# Driver_Circuit.net
KiCad netlist of a schematic drawn in Altium Designer
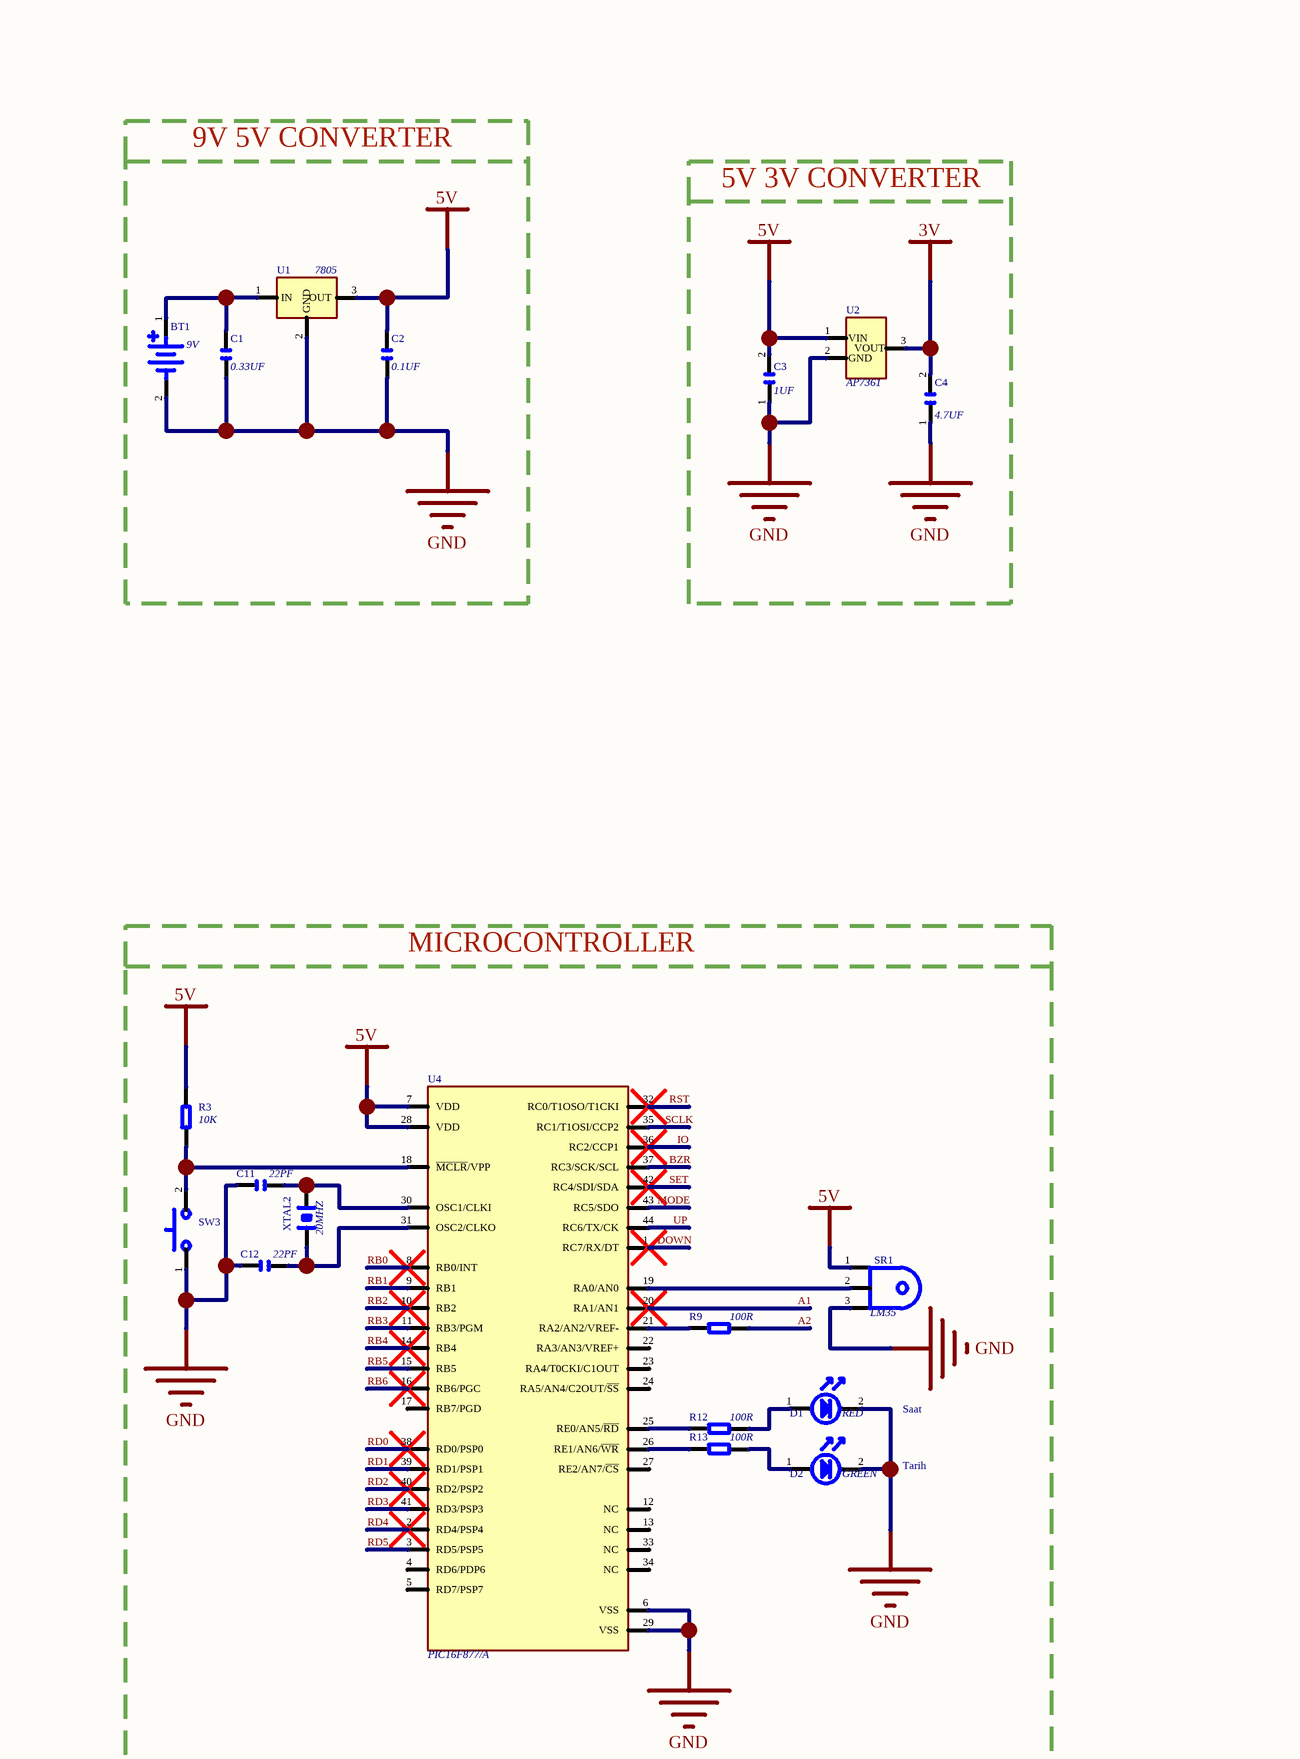
[diagram p0: Driver Circuit.SchDoc, top left]
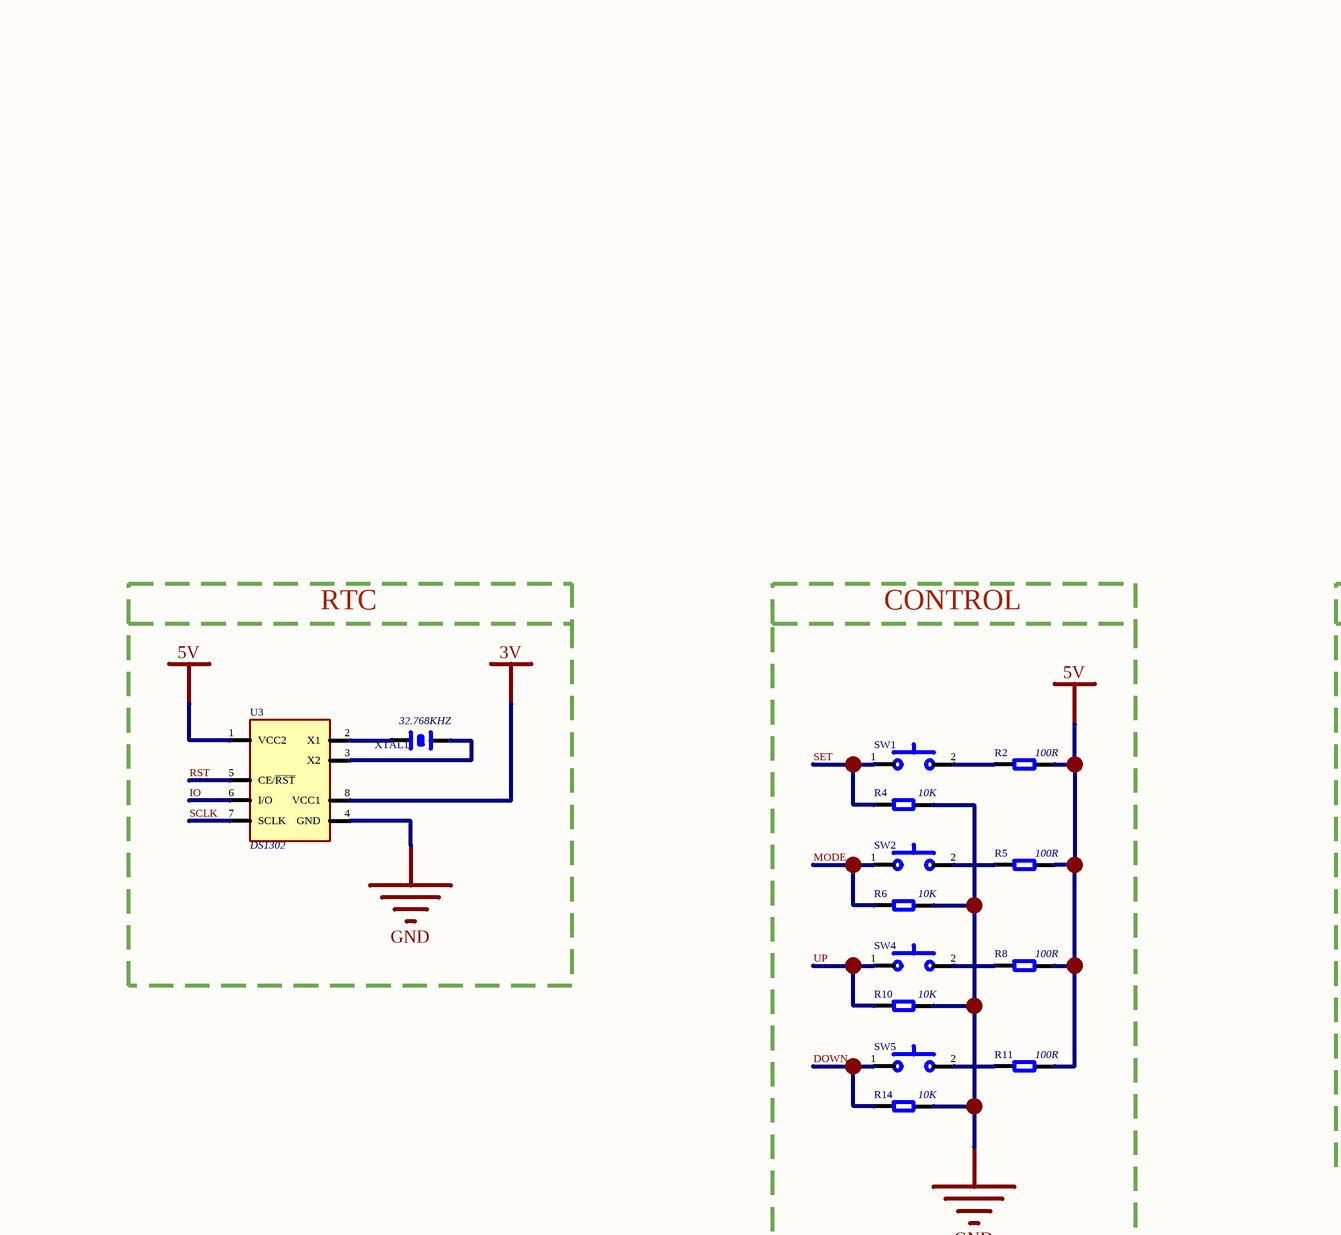
[diagram p1: Driver Circuit.SchDoc, top middle]
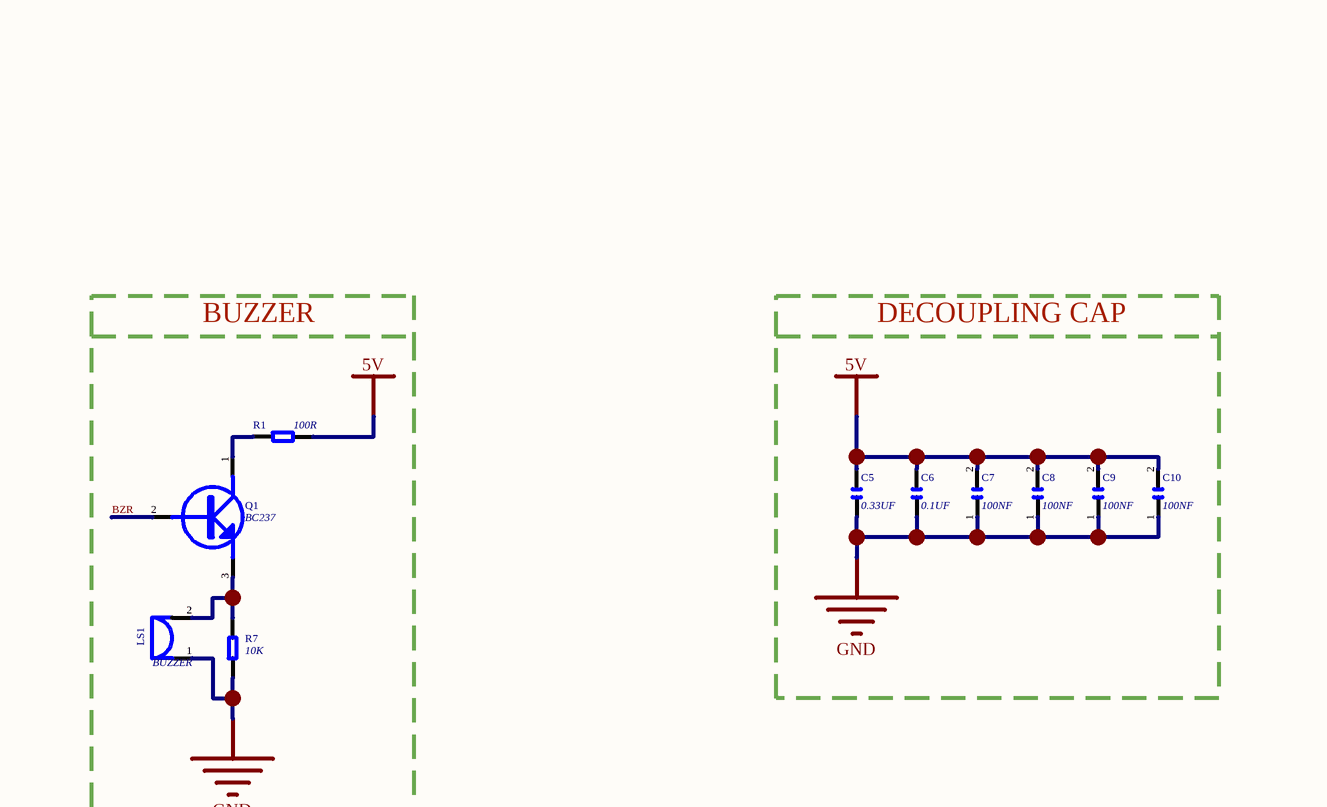
[diagram p2: Driver Circuit.SchDoc, top right]
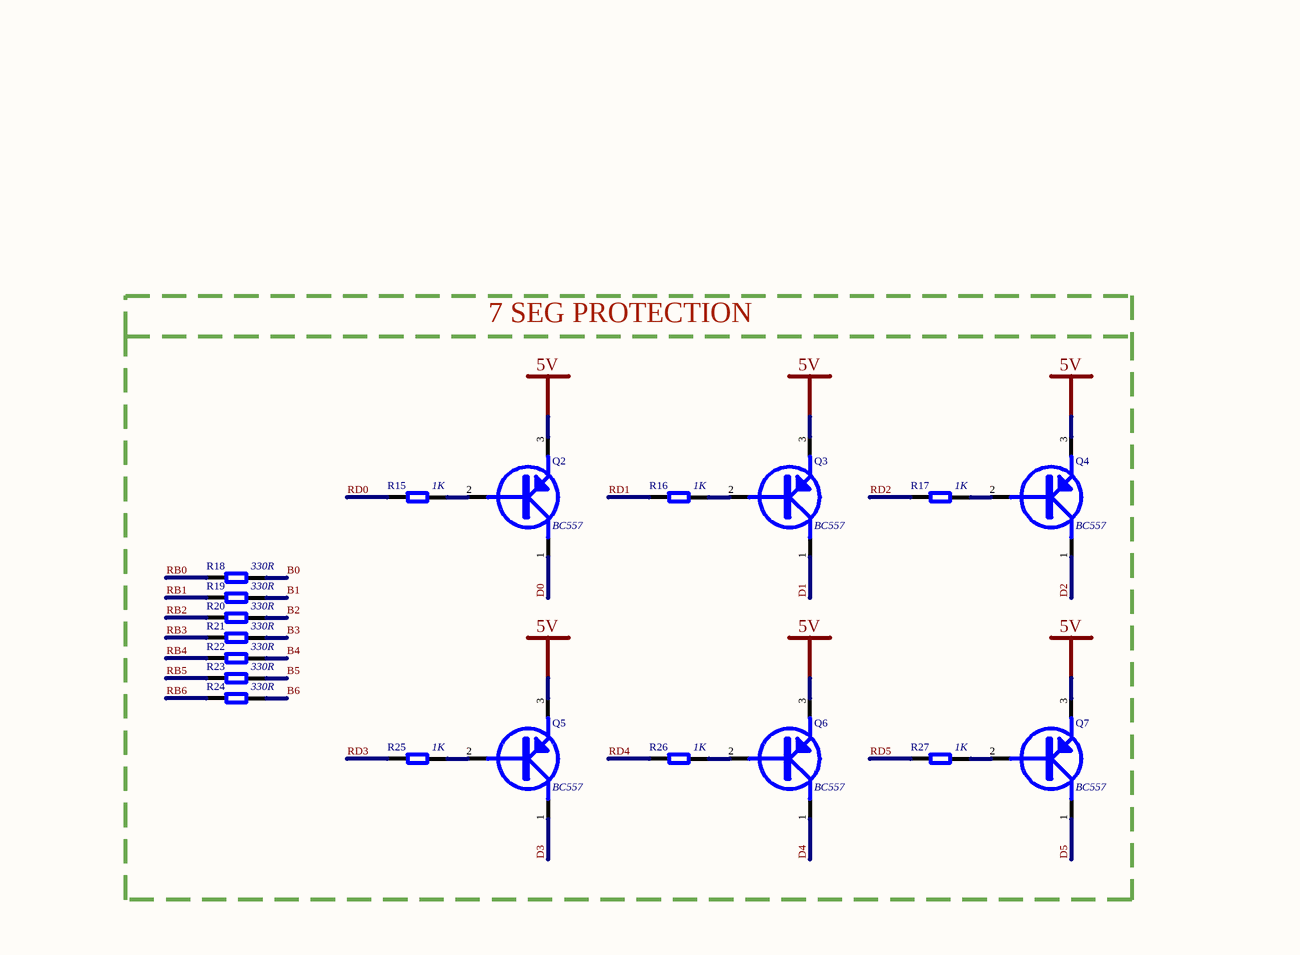
[diagram p3: Driver Circuit.SchDoc, centre left]
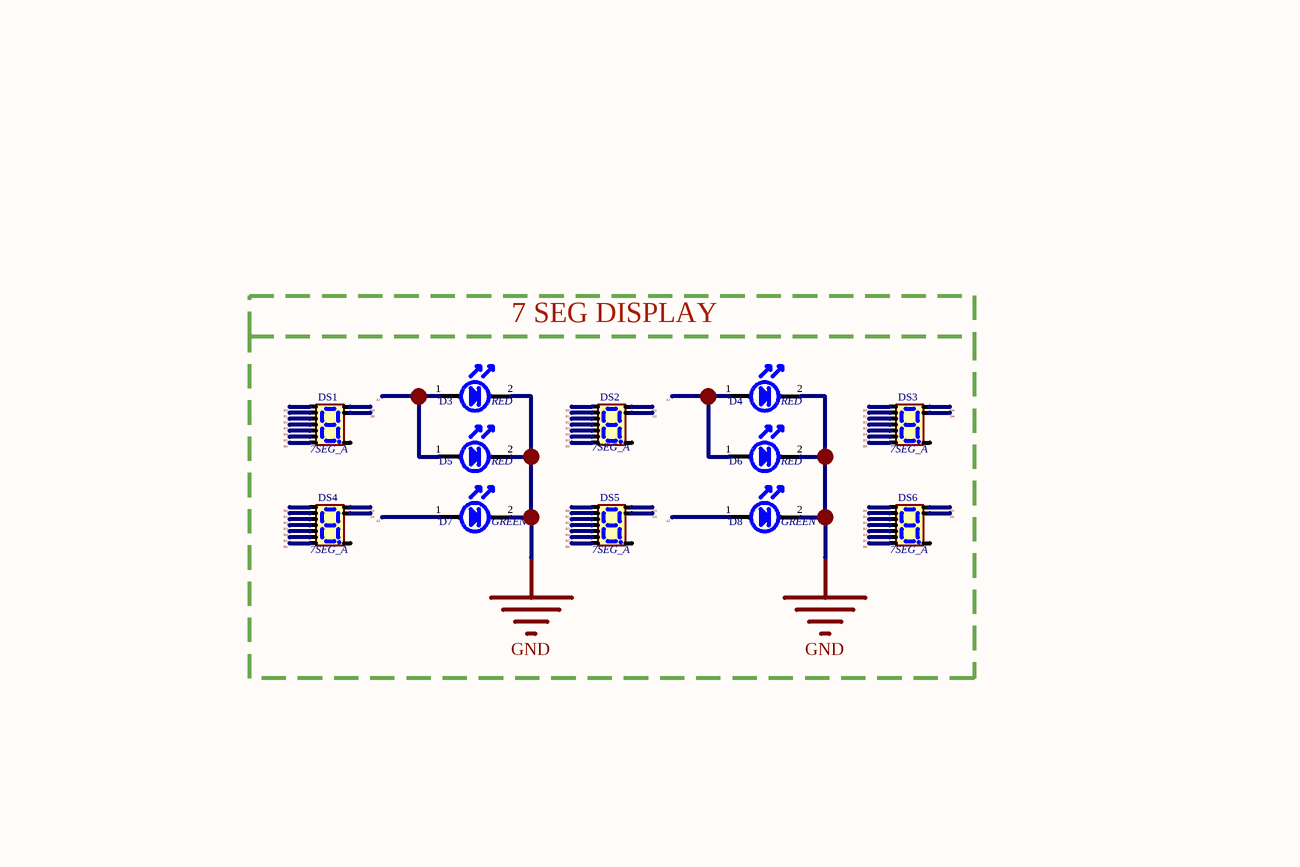
[diagram p4: Driver Circuit.SchDoc, centre middle]

(export (version "E")
  (design (tool "Eeschema 10.0.6"))
  (components
    (comp (ref "BT1")
      (value "9V")
      (footprint "BATTERY_9V")
      (fields
        (field (name "MANUFACTURER") "Memory Protection Devices")
        (field (name "MANUFACTURER PART NUMBER") "BH9VPC")
        (field (name "Comment") "BH9VPC & 6LF22XWA/B")
      )
      (libsource (lib "Integrated_Library") (part "BATTERY_9V"))
    )
    (comp (ref "C1")
      (value "GRM033R60J334ME90D")
      (footprint "CAP_0603")
      (description "CAP CER 0.33UF %20 0603 SMD")
      (fields
        (field (name "MANUFACTURER") "Murata")
        (field (name "TOLERANCE") "20%")
        (field (name "CAPACITOR") "0.33UF")
      )
      (libsource (lib "Integrated_Library") (part "0603_CAP_CER  UF_0.33"))
    )
    (comp (ref "C2")
      (value "GRM033R60J104KE19D")
      (footprint "CAP_0603")
      (description "CAP CER 0.1UF %10 0603 SMD")
      (fields
        (field (name "MANUFACTURER") "Murata")
        (field (name "TOLERANCE") "10%")
        (field (name "CAPACITOR") "0.1UF")
      )
      (libsource (lib "Integrated_Library") (part "0603_CAP_CER  UF_0.1"))
    )
    (comp (ref "C3")
      (value "CL21B105KBFNNNE")
      (footprint "CAP_0805")
      (description "CAP CER 1UF %10 0805 SMD")
      (fields (field (name "CAPACITOR") "1UF"))
      (libsource (lib "Integrated_Library") (part "0805_CAP_CER  UF_1"))
    )
    (comp (ref "C4")
      (value "CL21A475KAQNNNE")
      (footprint "CAP_0805")
      (description "CAP CER 4.7UF %10 0805 SMD")
      (fields (field (name "CAPACITOR") "4.7UF"))
      (libsource (lib "Integrated_Library") (part "0805_CAP_CER  UF_4.7"))
    )
    (comp (ref "C5")
      (value "GRM033R60J334ME90D")
      (footprint "CAP_0603")
      (description "CAP CER 0.33UF %20 0603 SMD")
      (fields
        (field (name "MANUFACTURER") "Murata")
        (field (name "TOLERANCE") "20%")
        (field (name "CAPACITOR") "0.33UF")
      )
      (libsource (lib "Integrated_Library") (part "0603_CAP_CER  UF_0.33"))
    )
    (comp (ref "C6")
      (value "GRM033R60J104KE19D")
      (footprint "CAP_0603")
      (description "CAP CER 0.1UF %10 0603 SMD")
      (fields
        (field (name "MANUFACTURER") "Murata")
        (field (name "TOLERANCE") "10%")
        (field (name "CAPACITOR") "0.1UF")
      )
      (libsource (lib "Integrated_Library") (part "0603_CAP_CER  UF_0.1"))
    )
    (comp (ref "C7")
      (value "C0603C104K5RACTU")
      (footprint "CAP_0603")
      (description "CAP CER 100NF %10 0603 SMD")
      (fields (field (name "CAPACITOR") "100NF"))
      (libsource (lib "Integrated_Library") (part "0603_CAP_CER  NF_100"))
    )
    (comp (ref "C8")
      (value "C0603C104K5RACTU")
      (footprint "CAP_0603")
      (description "CAP CER 100NF %10 0603 SMD")
      (fields (field (name "CAPACITOR") "100NF"))
      (libsource (lib "Integrated_Library") (part "0603_CAP_CER  NF_100"))
    )
    (comp (ref "C9")
      (value "C0603C104K5RACTU")
      (footprint "CAP_0603")
      (description "CAP CER 100NF %10 0603 SMD")
      (fields (field (name "CAPACITOR") "100NF"))
      (libsource (lib "Integrated_Library") (part "0603_CAP_CER  NF_100"))
    )
    (comp (ref "C10")
      (value "C0603C104K5RACTU")
      (footprint "CAP_0603")
      (description "CAP CER 100NF %10 0603 SMD")
      (fields (field (name "CAPACITOR") "100NF"))
      (libsource (lib "Integrated_Library") (part "0603_CAP_CER  NF_100"))
    )
    (comp (ref "C11")
      (value "GRM0335C1H220JA01D")
      (footprint "CAP_0603")
      (description "CAP CER 22PF %5 0603 SMD")
      (fields
        (field (name "MANUFACTURER") "Murata")
        (field (name "TOLERANCE") "5%")
        (field (name "CAPACITOR") "22PF")
      )
      (libsource (lib "Integrated_Library") (part "0603_CAP_CER  PF_22"))
    )
    (comp (ref "C12")
      (value "GRM0335C1H220JA01D")
      (footprint "CAP_0603")
      (description "CAP CER 22PF %5 0603 SMD")
      (fields
        (field (name "MANUFACTURER") "Murata")
        (field (name "TOLERANCE") "5%")
        (field (name "CAPACITOR") "22PF")
      )
      (libsource (lib "Integrated_Library") (part "0603_CAP_CER  PF_22"))
    )
    (comp (ref "D1")
      (value "LTST-C170KRKT")
      (footprint "LED RED_0805")
      (description "Red 631nm LED Indication - Discrete 2V 0805 (2012 Metric)")
      (fields (field (name "MANUFACTURER") "Vishay Lite-On") (field (name "DIODE") "RED"))
      (libsource (lib "Integrated_Library") (part "LED_0805_RED"))
    )
    (comp (ref "D2")
      (value "LTST-C171GKT")
      (footprint "LED GREEN_0805")
      (description "Green 569nm LED Indication - Discrete 2.1V 0805 (2012 Metric)")
      (fields (field (name "MANUFACTURER") "Vishay Lite-On") (field (name "DIODE") "GREEN"))
      (libsource (lib "Integrated_Library") (part "LED_0805_GREEN"))
    )
    (comp (ref "D3")
      (value "LTST-C170KRKT")
      (footprint "LED RED_0805")
      (description "Red 631nm LED Indication - Discrete 2V 0805 (2012 Metric)")
      (fields (field (name "MANUFACTURER") "Vishay Lite-On") (field (name "DIODE") "RED"))
      (libsource (lib "Integrated_Library") (part "LED_0805_RED"))
    )
    (comp (ref "D4")
      (value "LTST-C170KRKT")
      (footprint "LED RED_0805")
      (description "Red 631nm LED Indication - Discrete 2V 0805 (2012 Metric)")
      (fields (field (name "MANUFACTURER") "Vishay Lite-On") (field (name "DIODE") "RED"))
      (libsource (lib "Integrated_Library") (part "LED_0805_RED"))
    )
    (comp (ref "D5")
      (value "LTST-C170KRKT")
      (footprint "LED RED_0805")
      (description "Red 631nm LED Indication - Discrete 2V 0805 (2012 Metric)")
      (fields (field (name "MANUFACTURER") "Vishay Lite-On") (field (name "DIODE") "RED"))
      (libsource (lib "Integrated_Library") (part "LED_0805_RED"))
    )
    (comp (ref "D6")
      (value "LTST-C170KRKT")
      (footprint "LED RED_0805")
      (description "Red 631nm LED Indication - Discrete 2V 0805 (2012 Metric)")
      (fields (field (name "MANUFACTURER") "Vishay Lite-On") (field (name "DIODE") "RED"))
      (libsource (lib "Integrated_Library") (part "LED_0805_RED"))
    )
    (comp (ref "D7")
      (value "LTST-C171GKT")
      (footprint "LED GREEN_0805")
      (description "Green 569nm LED Indication - Discrete 2.1V 0805 (2012 Metric)")
      (fields (field (name "MANUFACTURER") "Vishay Lite-On") (field (name "DIODE") "GREEN"))
      (libsource (lib "Integrated_Library") (part "LED_0805_GREEN"))
    )
    (comp (ref "D8")
      (value "LTST-C171GKT")
      (footprint "LED GREEN_0805")
      (description "Green 569nm LED Indication - Discrete 2.1V 0805 (2012 Metric)")
      (fields (field (name "MANUFACTURER") "Vishay Lite-On") (field (name "DIODE") "GREEN"))
      (libsource (lib "Integrated_Library") (part "LED_0805_GREEN"))
    )
    (comp (ref "DS1")
      (value "7SEG_A")
      (footprint "7 SEG_CA_SMD_ACSX03-41")
      (fields
        (field (name "MANUFACTURER") "Kingbright")
        (field (name "MANUFACTURER PART NUMBER") "ACSA03-41SURKWA-F01")
      )
      (libsource (lib "Integrated_Library") (part "7 SEG DISP_CA_SMD"))
    )
    (comp (ref "DS2")
      (value "7SEG_A")
      (footprint "7 SEG_CA_SMD_ACSX03-41")
      (fields
        (field (name "MANUFACTURER") "Kingbright")
        (field (name "MANUFACTURER PART NUMBER") "ACSA03-41SURKWA-F01")
      )
      (libsource (lib "Integrated_Library") (part "7 SEG DISP_CA_SMD"))
    )
    (comp (ref "DS3")
      (value "7SEG_A")
      (footprint "7 SEG_CA_SMD_ACSX03-41")
      (fields
        (field (name "MANUFACTURER") "Kingbright")
        (field (name "MANUFACTURER PART NUMBER") "ACSA03-41SURKWA-F01")
      )
      (libsource (lib "Integrated_Library") (part "7 SEG DISP_CA_SMD"))
    )
    (comp (ref "DS4")
      (value "7SEG_A")
      (footprint "7 SEG_CA_SMD_ACSX03-41")
      (fields
        (field (name "MANUFACTURER") "Kingbright")
        (field (name "MANUFACTURER PART NUMBER") "ACSA03-41SURKWA-F01")
      )
      (libsource (lib "Integrated_Library") (part "7 SEG DISP_CA_SMD"))
    )
    (comp (ref "DS5")
      (value "7SEG_A")
      (footprint "7 SEG_CA_SMD_ACSX03-41")
      (fields
        (field (name "MANUFACTURER") "Kingbright")
        (field (name "MANUFACTURER PART NUMBER") "ACSA03-41SURKWA-F01")
      )
      (libsource (lib "Integrated_Library") (part "7 SEG DISP_CA_SMD"))
    )
    (comp (ref "DS6")
      (value "7SEG_A")
      (footprint "7 SEG_CA_SMD_ACSX03-41")
      (fields
        (field (name "MANUFACTURER") "Kingbright")
        (field (name "MANUFACTURER PART NUMBER") "ACSA03-41SURKWA-F01")
      )
      (libsource (lib "Integrated_Library") (part "7 SEG DISP_CA_SMD"))
    )
    (comp (ref "LS1")
      (value "BUZZER")
      (footprint "BUZZER_5V")
      (fields
        (field (name "MANUFACTURER") "Projects Unlimited")
        (field (name "MANUFACTURER PART NUMBER") "AI-1027-TWT-5V-R")
      )
      (libsource (lib "Integrated_Library") (part "BUZZER_5V"))
    )
    (comp (ref "Q1")
      (value "BC237")
      (footprint "TO-92")
      (description "Bipolar (BJT) Transistor NPN 45 V 100 mA 200MHz 350 mW Through Hole TO-92 (TO-226)")
      (fields
        (field (name "MANUFACTURER") "ON Semiconductor")
        (field (name "MANUFACTURER PART NUMBER") "BC237G")
      )
      (libsource (lib "Integrated_Library") (part "BC237"))
    )
    (comp (ref "Q2")
      (value "BC557")
      (footprint "TO-92-3")
      (description "Trans GP BJT PNP 45V 0.1A 500mW 3-Pin TO-92 Fan-Fold")
      (fields
        (field (name "MANUFACTURER") "ON Semiconductor / Fairchild")
        (field (name "MANUFACTURER PART NUMBER") "BC557BTA")
      )
      (libsource (lib "Integrated_Library") (part "BC557"))
    )
    (comp (ref "Q3")
      (value "BC557")
      (footprint "TO-92-3")
      (description "Trans GP BJT PNP 45V 0.1A 500mW 3-Pin TO-92 Fan-Fold")
      (fields
        (field (name "MANUFACTURER") "ON Semiconductor / Fairchild")
        (field (name "MANUFACTURER PART NUMBER") "BC557BTA")
      )
      (libsource (lib "Integrated_Library") (part "BC557"))
    )
    (comp (ref "Q4")
      (value "BC557")
      (footprint "TO-92-3")
      (description "Trans GP BJT PNP 45V 0.1A 500mW 3-Pin TO-92 Fan-Fold")
      (fields
        (field (name "MANUFACTURER") "ON Semiconductor / Fairchild")
        (field (name "MANUFACTURER PART NUMBER") "BC557BTA")
      )
      (libsource (lib "Integrated_Library") (part "BC557"))
    )
    (comp (ref "Q5")
      (value "BC557")
      (footprint "TO-92-3")
      (description "Trans GP BJT PNP 45V 0.1A 500mW 3-Pin TO-92 Fan-Fold")
      (fields
        (field (name "MANUFACTURER") "ON Semiconductor / Fairchild")
        (field (name "MANUFACTURER PART NUMBER") "BC557BTA")
      )
      (libsource (lib "Integrated_Library") (part "BC557"))
    )
    (comp (ref "Q6")
      (value "BC557")
      (footprint "TO-92-3")
      (description "Trans GP BJT PNP 45V 0.1A 500mW 3-Pin TO-92 Fan-Fold")
      (fields
        (field (name "MANUFACTURER") "ON Semiconductor / Fairchild")
        (field (name "MANUFACTURER PART NUMBER") "BC557BTA")
      )
      (libsource (lib "Integrated_Library") (part "BC557"))
    )
    (comp (ref "Q7")
      (value "BC557")
      (footprint "TO-92-3")
      (description "Trans GP BJT PNP 45V 0.1A 500mW 3-Pin TO-92 Fan-Fold")
      (fields
        (field (name "MANUFACTURER") "ON Semiconductor / Fairchild")
        (field (name "MANUFACTURER PART NUMBER") "BC557BTA")
      )
      (libsource (lib "Integrated_Library") (part "BC557"))
    )
    (comp (ref "R1")
      (value "RC0603JR-07100RL")
      (footprint "RES_0603")
      (description "RES 100R %5 0603 SMD")
      (fields
        (field (name "MANUFACTURER") "Yageo")
        (field (name "TOLERANCE") "5%")
        (field (name "RESISTOR") "100R")
      )
      (libsource (lib "Integrated_Library") (part "0603_RES  R_100"))
    )
    (comp (ref "R2")
      (value "RC0603JR-07100RL")
      (footprint "RES_0603")
      (description "RES 100R %5 0603 SMD")
      (fields
        (field (name "MANUFACTURER") "Yageo")
        (field (name "TOLERANCE") "5%")
        (field (name "RESISTOR") "100R")
      )
      (libsource (lib "Integrated_Library") (part "0603_RES  R_100"))
    )
    (comp (ref "R3")
      (value "RC0603FR-0710KL")
      (footprint "RES_0603")
      (description "RES 10K %1 0603 SMD")
      (fields
        (field (name "MANUFACTURER") "Yageo")
        (field (name "TOLERANCE") "1%")
        (field (name "RESISTOR") "10K")
      )
      (libsource (lib "Integrated_Library") (part "0603_RES  K_10"))
    )
    (comp (ref "R4")
      (value "RC0603FR-0710KL")
      (footprint "RES_0603")
      (description "RES 10K %1 0603 SMD")
      (fields
        (field (name "MANUFACTURER") "Yageo")
        (field (name "TOLERANCE") "1%")
        (field (name "RESISTOR") "10K")
      )
      (libsource (lib "Integrated_Library") (part "0603_RES  K_10"))
    )
    (comp (ref "R5")
      (value "RC0603JR-07100RL")
      (footprint "RES_0603")
      (description "RES 100R %5 0603 SMD")
      (fields
        (field (name "MANUFACTURER") "Yageo")
        (field (name "TOLERANCE") "5%")
        (field (name "RESISTOR") "100R")
      )
      (libsource (lib "Integrated_Library") (part "0603_RES  R_100"))
    )
    (comp (ref "R6")
      (value "RC0603FR-0710KL")
      (footprint "RES_0603")
      (description "RES 10K %1 0603 SMD")
      (fields
        (field (name "MANUFACTURER") "Yageo")
        (field (name "TOLERANCE") "1%")
        (field (name "RESISTOR") "10K")
      )
      (libsource (lib "Integrated_Library") (part "0603_RES  K_10"))
    )
    (comp (ref "R7")
      (value "RC0603FR-0710KL")
      (footprint "RES_0603")
      (description "RES 10K %1 0603 SMD")
      (fields
        (field (name "MANUFACTURER") "Yageo")
        (field (name "TOLERANCE") "1%")
        (field (name "RESISTOR") "10K")
      )
      (libsource (lib "Integrated_Library") (part "0603_RES  K_10"))
    )
    (comp (ref "R8")
      (value "RC0603JR-07100RL")
      (footprint "RES_0603")
      (description "RES 100R %5 0603 SMD")
      (fields
        (field (name "MANUFACTURER") "Yageo")
        (field (name "TOLERANCE") "5%")
        (field (name "RESISTOR") "100R")
      )
      (libsource (lib "Integrated_Library") (part "0603_RES  R_100"))
    )
    (comp (ref "R9")
      (value "RC0603JR-07100RL")
      (footprint "RES_0603")
      (description "RES 100R %5 0603 SMD")
      (fields
        (field (name "MANUFACTURER") "Yageo")
        (field (name "TOLERANCE") "5%")
        (field (name "RESISTOR") "100R")
      )
      (libsource (lib "Integrated_Library") (part "0603_RES  R_100"))
    )
    (comp (ref "R10")
      (value "RC0603FR-0710KL")
      (footprint "RES_0603")
      (description "RES 10K %1 0603 SMD")
      (fields
        (field (name "MANUFACTURER") "Yageo")
        (field (name "TOLERANCE") "1%")
        (field (name "RESISTOR") "10K")
      )
      (libsource (lib "Integrated_Library") (part "0603_RES  K_10"))
    )
    (comp (ref "R11")
      (value "RC0603JR-07100RL")
      (footprint "RES_0603")
      (description "RES 100R %5 0603 SMD")
      (fields
        (field (name "MANUFACTURER") "Yageo")
        (field (name "TOLERANCE") "5%")
        (field (name "RESISTOR") "100R")
      )
      (libsource (lib "Integrated_Library") (part "0603_RES  R_100"))
    )
    (comp (ref "R12")
      (value "RC0603JR-07100RL")
      (footprint "RES_0603")
      (description "RES 100R %5 0603 SMD")
      (fields
        (field (name "MANUFACTURER") "Yageo")
        (field (name "TOLERANCE") "5%")
        (field (name "RESISTOR") "100R")
      )
      (libsource (lib "Integrated_Library") (part "0603_RES  R_100"))
    )
    (comp (ref "R13")
      (value "RC0603JR-07100RL")
      (footprint "RES_0603")
      (description "RES 100R %5 0603 SMD")
      (fields
        (field (name "MANUFACTURER") "Yageo")
        (field (name "TOLERANCE") "5%")
        (field (name "RESISTOR") "100R")
      )
      (libsource (lib "Integrated_Library") (part "0603_RES  R_100"))
    )
    (comp (ref "R14")
      (value "RC0603FR-0710KL")
      (footprint "RES_0603")
      (description "RES 10K %1 0603 SMD")
      (fields
        (field (name "MANUFACTURER") "Yageo")
        (field (name "TOLERANCE") "1%")
        (field (name "RESISTOR") "10K")
      )
      (libsource (lib "Integrated_Library") (part "0603_RES  K_10"))
    )
    (comp (ref "R15")
      (value "RC0603FR-071KL")
      (footprint "RES_0603")
      (description "RES 1K %1 0603 SMD")
      (fields
        (field (name "MANUFACTURER") "Yageo")
        (field (name "TOLERANCE") "1%")
        (field (name "RESISTOR") "1K")
      )
      (libsource (lib "Integrated_Library") (part "0603_RES  K_1"))
    )
    (comp (ref "R16")
      (value "RC0603FR-071KL")
      (footprint "RES_0603")
      (description "RES 1K %1 0603 SMD")
      (fields
        (field (name "MANUFACTURER") "Yageo")
        (field (name "TOLERANCE") "1%")
        (field (name "RESISTOR") "1K")
      )
      (libsource (lib "Integrated_Library") (part "0603_RES  K_1"))
    )
    (comp (ref "R17")
      (value "RC0603FR-071KL")
      (footprint "RES_0603")
      (description "RES 1K %1 0603 SMD")
      (fields
        (field (name "MANUFACTURER") "Yageo")
        (field (name "TOLERANCE") "1%")
        (field (name "RESISTOR") "1K")
      )
      (libsource (lib "Integrated_Library") (part "0603_RES  K_1"))
    )
    (comp (ref "R18")
      (value "RC0603JR-07330RL")
      (footprint "RES_0603")
      (description "RES 330R %5 0603 SMD")
      (fields
        (field (name "MANUFACTURER") "Yageo")
        (field (name "TOLERANCE") "5%")
        (field (name "RESISTOR") "330R")
      )
      (libsource (lib "Integrated_Library") (part "0603_RES  R_330"))
    )
    (comp (ref "R19")
      (value "RC0603JR-07330RL")
      (footprint "RES_0603")
      (description "RES 330R %5 0603 SMD")
      (fields
        (field (name "MANUFACTURER") "Yageo")
        (field (name "TOLERANCE") "5%")
        (field (name "RESISTOR") "330R")
      )
      (libsource (lib "Integrated_Library") (part "0603_RES  R_330"))
    )
    (comp (ref "R20")
      (value "RC0603JR-07330RL")
      (footprint "RES_0603")
      (description "RES 330R %5 0603 SMD")
      (fields
        (field (name "MANUFACTURER") "Yageo")
        (field (name "TOLERANCE") "5%")
        (field (name "RESISTOR") "330R")
      )
      (libsource (lib "Integrated_Library") (part "0603_RES  R_330"))
    )
    (comp (ref "R21")
      (value "RC0603JR-07330RL")
      (footprint "RES_0603")
      (description "RES 330R %5 0603 SMD")
      (fields
        (field (name "MANUFACTURER") "Yageo")
        (field (name "TOLERANCE") "5%")
        (field (name "RESISTOR") "330R")
      )
      (libsource (lib "Integrated_Library") (part "0603_RES  R_330"))
    )
    (comp (ref "R22")
      (value "RC0603JR-07330RL")
      (footprint "RES_0603")
      (description "RES 330R %5 0603 SMD")
      (fields
        (field (name "MANUFACTURER") "Yageo")
        (field (name "TOLERANCE") "5%")
        (field (name "RESISTOR") "330R")
      )
      (libsource (lib "Integrated_Library") (part "0603_RES  R_330"))
    )
    (comp (ref "R23")
      (value "RC0603JR-07330RL")
      (footprint "RES_0603")
      (description "RES 330R %5 0603 SMD")
      (fields
        (field (name "MANUFACTURER") "Yageo")
        (field (name "TOLERANCE") "5%")
        (field (name "RESISTOR") "330R")
      )
      (libsource (lib "Integrated_Library") (part "0603_RES  R_330"))
    )
    (comp (ref "R24")
      (value "RC0603JR-07330RL")
      (footprint "RES_0603")
      (description "RES 330R %5 0603 SMD")
      (fields
        (field (name "MANUFACTURER") "Yageo")
        (field (name "TOLERANCE") "5%")
        (field (name "RESISTOR") "330R")
      )
      (libsource (lib "Integrated_Library") (part "0603_RES  R_330"))
    )
    (comp (ref "R25")
      (value "RC0603FR-071KL")
      (footprint "RES_0603")
      (description "RES 1K %1 0603 SMD")
      (fields
        (field (name "MANUFACTURER") "Yageo")
        (field (name "TOLERANCE") "1%")
        (field (name "RESISTOR") "1K")
      )
      (libsource (lib "Integrated_Library") (part "0603_RES  K_1"))
    )
    (comp (ref "R26")
      (value "RC0603FR-071KL")
      (footprint "RES_0603")
      (description "RES 1K %1 0603 SMD")
      (fields
        (field (name "MANUFACTURER") "Yageo")
        (field (name "TOLERANCE") "1%")
        (field (name "RESISTOR") "1K")
      )
      (libsource (lib "Integrated_Library") (part "0603_RES  K_1"))
    )
    (comp (ref "R27")
      (value "RC0603FR-071KL")
      (footprint "RES_0603")
      (description "RES 1K %1 0603 SMD")
      (fields
        (field (name "MANUFACTURER") "Yageo")
        (field (name "TOLERANCE") "1%")
        (field (name "RESISTOR") "1K")
      )
      (libsource (lib "Integrated_Library") (part "0603_RES  K_1"))
    )
    (comp (ref "SR1")
      (value "LM35")
      (footprint "TO-92-3")
      (description "Temperature Sensor Analog, Local 0°C ~ 100°C 10mV/°C TO-92-3")
      (fields
        (field (name "MANUFACTURER") "TI National Semiconductor")
        (field (name "MANUFACTURER PART NUMBER") "LM35DZ/NOPB")
      )
      (libsource (lib "Integrated_Library") (part "LM35DZ"))
    )
    (comp (ref "SW1")
      (value "PTS526 SMG15 SMTR2 LFS")
      (footprint "BUTTON_SMD_PTS526-SMG15")
      (description "Tactile Switch SPST-NO Top Actuated Surface Mount")
      (fields
        (field (name "MANUFACTURER") "ITT C&K")
        (field (name "MANUFACTURER PART NUMBER") "PTS526SMG15SMTR2LFS")
      )
      (libsource (lib "Integrated_Library") (part "BUTTON_SMD"))
    )
    (comp (ref "SW2")
      (value "PTS526 SMG15 SMTR2 LFS")
      (footprint "BUTTON_SMD_PTS526-SMG15")
      (description "Tactile Switch SPST-NO Top Actuated Surface Mount")
      (fields
        (field (name "MANUFACTURER") "ITT C&K")
        (field (name "MANUFACTURER PART NUMBER") "PTS526SMG15SMTR2LFS")
      )
      (libsource (lib "Integrated_Library") (part "BUTTON_SMD"))
    )
    (comp (ref "SW3")
      (value "PTS526 SMG15 SMTR2 LFS")
      (footprint "BUTTON_SMD_PTS526-SMG15")
      (description "Tactile Switch SPST-NO Top Actuated Surface Mount")
      (fields
        (field (name "MANUFACTURER") "ITT C&K")
        (field (name "MANUFACTURER PART NUMBER") "PTS526SMG15SMTR2LFS")
      )
      (libsource (lib "Integrated_Library") (part "BUTTON_SMD"))
    )
    (comp (ref "SW4")
      (value "PTS526 SMG15 SMTR2 LFS")
      (footprint "BUTTON_SMD_PTS526-SMG15")
      (description "Tactile Switch SPST-NO Top Actuated Surface Mount")
      (fields
        (field (name "MANUFACTURER") "ITT C&K")
        (field (name "MANUFACTURER PART NUMBER") "PTS526SMG15SMTR2LFS")
      )
      (libsource (lib "Integrated_Library") (part "BUTTON_SMD"))
    )
    (comp (ref "SW5")
      (value "PTS526 SMG15 SMTR2 LFS")
      (footprint "BUTTON_SMD_PTS526-SMG15")
      (description "Tactile Switch SPST-NO Top Actuated Surface Mount")
      (fields
        (field (name "MANUFACTURER") "ITT C&K")
        (field (name "MANUFACTURER PART NUMBER") "PTS526SMG15SMTR2LFS")
      )
      (libsource (lib "Integrated_Library") (part "BUTTON_SMD"))
    )
    (comp (ref "U1")
      (value "7805")
      (footprint "7805_D2PAK_CD2T")
      (description "Linear Voltage Regulator IC Positive Fixed 1 Output 5V 1.5A D2PAK")
      (fields
        (field (name "MANUFACTURER") "STMicroelectronics")
        (field (name "MANUFACTURER PART NUMBER") "L7805ACD2T-TR")
      )
      (libsource (lib "Integrated_Library") (part "7805"))
    )
    (comp (ref "U2")
      (value "AP7361")
      (footprint "SOT-223")
      (description "AP7361 Series 3.3 V 1 A Low SMT Dropout Fixed-Mode Regulator - SOT-223")
      (fields (field (name "Comment") "AP7361-33E-13"))
      (libsource (lib "Integrated_Library") (part "AP7361-33E-13"))
    )
    (comp (ref "U3")
      (value "DS1302")
      (footprint "SOIC-8")
      (description "IC RTC CLK/CALENDAR SER 8-SOIC")
      (fields (field (name "MANUFACTURER") "Maxim") (field (name "MANUFACTURER PART NUMBER") "DS1302Z/T&R"))
      (libsource (lib "Integrated_Library") (part "DS1302_SMD"))
    )
    (comp (ref "U4")
      (value "PIC16F877/A")
      (footprint "TQFP-44")
      (description "PIC16F Series 14 kB Flash 368 B RAM 20 MHz 8-Bit Microcontroller - TQFP-44")
      (fields
        (field (name "MANUFACTURER") "Microchip")
        (field (name "MANUFACTURER PART NUMBER") "PIC16F877-20/PT")
      )
      (libsource (lib "Integrated_Library") (part "PIC16F877/A_SMD"))
    )
    (comp (ref "XTAL1")
      (value "ABS05-32.768KHZ-T")
      (footprint "ABS05")
      (description "ABRACON - ABS05-32.768KHZ-T - Crystal, 32.768 kHz, SMD, 1.6mm x 1mm, 12.5 pF, 20 ppm, ABS05 Series")
      (fields
        (field (name "MANUFACTURER") "Abracon")
        (field (name "TOLERANCE") "20ppm")
        (field (name "CRYSTAL") "32.768KHZ")
      )
      (libsource (lib "Integrated_Library") (part "CRYSTAL_32.768 KHZ_SMD"))
    )
    (comp (ref "XTAL2")
      (value "ECS-200-20-23A-EN-TR")
      (footprint "CRYSTAL_2 SMD")
      (description "20 MHz ±30ppm Crystal 20pF 30 Ohms 2-SMD, No Lead")
      (fields (field (name "MANUFACTURER") "ECS International") (field (name "CRYSTAL") "20MHZ"))
      (libsource (lib "Integrated_Library") (part "CRYSTAL_20 MHZ_20PF_2 SMD"))
    )
  )
  (nets
    (net (code "1") (name "/A1") (class "Default")
      (node (ref "D3") (pin "1") (pinfunction "1_1") (pintype "passive"))
      (node (ref "D4") (pin "1") (pinfunction "1_1") (pintype "passive"))
      (node (ref "D5") (pin "1") (pinfunction "1_1") (pintype "passive"))
      (node (ref "D6") (pin "1") (pinfunction "1_1") (pintype "passive"))
      (node (ref "U4") (pin "20") (pinfunction "RA1/AN1_20") (pintype "passive"))
    )
    (net (code "2") (name "/A2") (class "Default")
      (node (ref "D7") (pin "1") (pinfunction "1_1") (pintype "passive"))
      (node (ref "D8") (pin "1") (pinfunction "1_1") (pintype "passive"))
      (node (ref "R9") (pin "2") (pinfunction "2_2") (pintype "passive"))
    )
    (net (code "3") (name "/B0") (class "Default")
      (node (ref "DS1") (pin "A") (pinfunction "A_A") (pintype "passive"))
      (node (ref "DS2") (pin "A") (pinfunction "A_A") (pintype "passive"))
      (node (ref "DS3") (pin "A") (pinfunction "A_A") (pintype "passive"))
      (node (ref "DS4") (pin "A") (pinfunction "A_A") (pintype "passive"))
      (node (ref "DS5") (pin "A") (pinfunction "A_A") (pintype "passive"))
      (node (ref "DS6") (pin "A") (pinfunction "A_A") (pintype "passive"))
      (node (ref "R18") (pin "2") (pinfunction "2_2") (pintype "passive"))
    )
    (net (code "4") (name "/B1") (class "Default")
      (node (ref "DS1") (pin "B") (pinfunction "B_B") (pintype "passive"))
      (node (ref "DS2") (pin "B") (pinfunction "B_B") (pintype "passive"))
      (node (ref "DS3") (pin "B") (pinfunction "B_B") (pintype "passive"))
      (node (ref "DS4") (pin "B") (pinfunction "B_B") (pintype "passive"))
      (node (ref "DS5") (pin "B") (pinfunction "B_B") (pintype "passive"))
      (node (ref "DS6") (pin "B") (pinfunction "B_B") (pintype "passive"))
      (node (ref "R19") (pin "2") (pinfunction "2_2") (pintype "passive"))
    )
    (net (code "5") (name "/B2") (class "Default")
      (node (ref "DS1") (pin "C") (pinfunction "C_C") (pintype "passive"))
      (node (ref "DS2") (pin "C") (pinfunction "C_C") (pintype "passive"))
      (node (ref "DS3") (pin "C") (pinfunction "C_C") (pintype "passive"))
      (node (ref "DS4") (pin "C") (pinfunction "C_C") (pintype "passive"))
      (node (ref "DS5") (pin "C") (pinfunction "C_C") (pintype "passive"))
      (node (ref "DS6") (pin "C") (pinfunction "C_C") (pintype "passive"))
      (node (ref "R20") (pin "2") (pinfunction "2_2") (pintype "passive"))
    )
    (net (code "6") (name "/B3") (class "Default")
      (node (ref "DS1") (pin "D") (pinfunction "D_D") (pintype "passive"))
      (node (ref "DS2") (pin "D") (pinfunction "D_D") (pintype "passive"))
      (node (ref "DS3") (pin "D") (pinfunction "D_D") (pintype "passive"))
      (node (ref "DS4") (pin "D") (pinfunction "D_D") (pintype "passive"))
      (node (ref "DS5") (pin "D") (pinfunction "D_D") (pintype "passive"))
      (node (ref "DS6") (pin "D") (pinfunction "D_D") (pintype "passive"))
      (node (ref "R21") (pin "2") (pinfunction "2_2") (pintype "passive"))
    )
    (net (code "7") (name "/B4") (class "Default")
      (node (ref "DS1") (pin "E") (pinfunction "E_E") (pintype "passive"))
      (node (ref "DS2") (pin "E") (pinfunction "E_E") (pintype "passive"))
      (node (ref "DS3") (pin "E") (pinfunction "E_E") (pintype "passive"))
      (node (ref "DS4") (pin "E") (pinfunction "E_E") (pintype "passive"))
      (node (ref "DS5") (pin "E") (pinfunction "E_E") (pintype "passive"))
      (node (ref "DS6") (pin "E") (pinfunction "E_E") (pintype "passive"))
      (node (ref "R22") (pin "2") (pinfunction "2_2") (pintype "passive"))
    )
    (net (code "8") (name "/B5") (class "Default")
      (node (ref "DS1") (pin "F") (pinfunction "F_F") (pintype "passive"))
      (node (ref "DS2") (pin "F") (pinfunction "F_F") (pintype "passive"))
      (node (ref "DS3") (pin "F") (pinfunction "F_F") (pintype "passive"))
      (node (ref "DS4") (pin "F") (pinfunction "F_F") (pintype "passive"))
      (node (ref "DS5") (pin "F") (pinfunction "F_F") (pintype "passive"))
      (node (ref "DS6") (pin "F") (pinfunction "F_F") (pintype "passive"))
      (node (ref "R23") (pin "2") (pinfunction "2_2") (pintype "passive"))
    )
    (net (code "9") (name "/B6") (class "Default")
      (node (ref "DS1") (pin "G") (pinfunction "G_G") (pintype "passive"))
      (node (ref "DS2") (pin "G") (pinfunction "G_G") (pintype "passive"))
      (node (ref "DS3") (pin "G") (pinfunction "G_G") (pintype "passive"))
      (node (ref "DS4") (pin "G") (pinfunction "G_G") (pintype "passive"))
      (node (ref "DS5") (pin "G") (pinfunction "G_G") (pintype "passive"))
      (node (ref "DS6") (pin "G") (pinfunction "G_G") (pintype "passive"))
      (node (ref "R24") (pin "2") (pinfunction "2_2") (pintype "passive"))
    )
    (net (code "10") (name "/BZR") (class "Default")
      (node (ref "Q1") (pin "2") (pinfunction "B_2") (pintype "passive"))
      (node (ref "U4") (pin "37") (pinfunction "RC3/SCK/SCL_37") (pintype "passive"))
    )
    (net (code "11") (name "/D0") (class "Default")
      (node (ref "DS1") (pin "VCC") (pinfunction "VCC_VCC") (pintype "passive"))
      (node (ref "Q2") (pin "1") (pinfunction "C_1") (pintype "passive"))
    )
    (net (code "12") (name "/D1") (class "Default")
      (node (ref "DS4") (pin "VCC") (pinfunction "VCC_VCC") (pintype "passive"))
      (node (ref "Q3") (pin "1") (pinfunction "C_1") (pintype "passive"))
    )
    (net (code "13") (name "/D2") (class "Default")
      (node (ref "DS2") (pin "VCC") (pinfunction "VCC_VCC") (pintype "passive"))
      (node (ref "Q4") (pin "1") (pinfunction "C_1") (pintype "passive"))
    )
    (net (code "14") (name "/D3") (class "Default")
      (node (ref "DS5") (pin "VCC") (pinfunction "VCC_VCC") (pintype "passive"))
      (node (ref "Q5") (pin "1") (pinfunction "C_1") (pintype "passive"))
    )
    (net (code "15") (name "/D4") (class "Default")
      (node (ref "DS3") (pin "VCC") (pinfunction "VCC_VCC") (pintype "passive"))
      (node (ref "Q6") (pin "1") (pinfunction "C_1") (pintype "passive"))
    )
    (net (code "16") (name "/D5") (class "Default")
      (node (ref "DS6") (pin "VCC") (pinfunction "VCC_VCC") (pintype "passive"))
      (node (ref "Q7") (pin "1") (pinfunction "C_1") (pintype "passive"))
    )
    (net (code "17") (name "/DOWN") (class "Default")
      (node (ref "R14") (pin "1") (pinfunction "1_1") (pintype "passive"))
      (node (ref "SW5") (pin "1") (pinfunction "1_1") (pintype "passive"))
      (node (ref "U4") (pin "1") (pinfunction "RC7/RX/DT_1") (pintype "passive"))
    )
    (net (code "18") (name "/IO") (class "Default")
      (node (ref "U3") (pin "6") (pinfunction "I/O_6") (pintype "passive"))
      (node (ref "U4") (pin "36") (pinfunction "RC2/CCP1_36") (pintype "passive"))
    )
    (net (code "19") (name "/MODE") (class "Default")
      (node (ref "R6") (pin "1") (pinfunction "1_1") (pintype "passive"))
      (node (ref "SW2") (pin "1") (pinfunction "1_1") (pintype "passive"))
      (node (ref "U4") (pin "43") (pinfunction "RC5/SDO_43") (pintype "passive"))
    )
    (net (code "20") (name "/RB0") (class "Default")
      (node (ref "R18") (pin "1") (pinfunction "1_1") (pintype "passive"))
      (node (ref "U4") (pin "8") (pinfunction "RB0/INT_8") (pintype "passive"))
    )
    (net (code "21") (name "/RB1") (class "Default")
      (node (ref "R19") (pin "1") (pinfunction "1_1") (pintype "passive"))
      (node (ref "U4") (pin "9") (pinfunction "RB1_9") (pintype "passive"))
    )
    (net (code "22") (name "/RB2") (class "Default")
      (node (ref "R20") (pin "1") (pinfunction "1_1") (pintype "passive"))
      (node (ref "U4") (pin "10") (pinfunction "RB2_10") (pintype "passive"))
    )
    (net (code "23") (name "/RB3") (class "Default")
      (node (ref "R21") (pin "1") (pinfunction "1_1") (pintype "passive"))
      (node (ref "U4") (pin "11") (pinfunction "RB3/PGM_11") (pintype "passive"))
    )
    (net (code "24") (name "/RB4") (class "Default")
      (node (ref "R22") (pin "1") (pinfunction "1_1") (pintype "passive"))
      (node (ref "U4") (pin "14") (pinfunction "RB4_14") (pintype "passive"))
    )
    (net (code "25") (name "/RB5") (class "Default")
      (node (ref "R23") (pin "1") (pinfunction "1_1") (pintype "passive"))
      (node (ref "U4") (pin "15") (pinfunction "RB5_15") (pintype "passive"))
    )
    (net (code "26") (name "/RB6") (class "Default")
      (node (ref "R24") (pin "1") (pinfunction "1_1") (pintype "passive"))
      (node (ref "U4") (pin "16") (pinfunction "RB6/PGC_16") (pintype "passive"))
    )
    (net (code "27") (name "/RD0") (class "Default")
      (node (ref "R15") (pin "1") (pinfunction "1_1") (pintype "passive"))
      (node (ref "U4") (pin "38") (pinfunction "RD0/PSP0_38") (pintype "passive"))
    )
    (net (code "28") (name "/RD1") (class "Default")
      (node (ref "R16") (pin "1") (pinfunction "1_1") (pintype "passive"))
      (node (ref "U4") (pin "39") (pinfunction "RD1/PSP1_39") (pintype "passive"))
    )
    (net (code "29") (name "/RD2") (class "Default")
      (node (ref "R17") (pin "1") (pinfunction "1_1") (pintype "passive"))
      (node (ref "U4") (pin "40") (pinfunction "RD2/PSP2_40") (pintype "passive"))
    )
    (net (code "30") (name "/RD3") (class "Default")
      (node (ref "R25") (pin "1") (pinfunction "1_1") (pintype "passive"))
      (node (ref "U4") (pin "41") (pinfunction "RD3/PSP3_41") (pintype "passive"))
    )
    (net (code "31") (name "/RD4") (class "Default")
      (node (ref "R26") (pin "1") (pinfunction "1_1") (pintype "passive"))
      (node (ref "U4") (pin "2") (pinfunction "RD4/PSP4_2") (pintype "passive"))
    )
    (net (code "32") (name "/RD5") (class "Default")
      (node (ref "R27") (pin "1") (pinfunction "1_1") (pintype "passive"))
      (node (ref "U4") (pin "3") (pinfunction "RD5/PSP5_3") (pintype "passive"))
    )
    (net (code "33") (name "/RST") (class "Default")
      (node (ref "U3") (pin "5") (pinfunction "CE/~{RST}_5") (pintype "passive"))
      (node (ref "U4") (pin "32") (pinfunction "RC0/T1OSO/T1CKI_32") (pintype "passive"))
    )
    (net (code "34") (name "/SCLK") (class "Default")
      (node (ref "U3") (pin "7") (pinfunction "SCLK_7") (pintype "passive"))
      (node (ref "U4") (pin "35") (pinfunction "RC1/T1OSI/CCP2_35") (pintype "passive"))
    )
    (net (code "35") (name "/SET") (class "Default")
      (node (ref "R4") (pin "1") (pinfunction "1_1") (pintype "passive"))
      (node (ref "SW1") (pin "1") (pinfunction "1_1") (pintype "passive"))
      (node (ref "U4") (pin "42") (pinfunction "RC4/SDI/SDA_42") (pintype "passive"))
    )
    (net (code "36") (name "/UP") (class "Default")
      (node (ref "R10") (pin "1") (pinfunction "1_1") (pintype "passive"))
      (node (ref "SW4") (pin "1") (pinfunction "1_1") (pintype "passive"))
      (node (ref "U4") (pin "44") (pinfunction "RC6/TX/CK_44") (pintype "passive"))
    )
    (net (code "37") (name "3V") (class "Default")
      (node (ref "C4") (pin "2") (pinfunction "2_2") (pintype "passive"))
      (node (ref "U2") (pin "3") (pinfunction "VOUT_3") (pintype "passive"))
      (node (ref "U3") (pin "8") (pinfunction "VCC1_8") (pintype "passive"))
    )
    (net (code "38") (name "5V") (class "Default")
      (node (ref "C10") (pin "2") (pinfunction "2_2") (pintype "passive"))
      (node (ref "C2") (pin "2") (pinfunction "2_2") (pintype "passive"))
      (node (ref "C3") (pin "2") (pinfunction "2_2") (pintype "passive"))
      (node (ref "C5") (pin "2") (pinfunction "2_2") (pintype "passive"))
      (node (ref "C6") (pin "2") (pinfunction "2_2") (pintype "passive"))
      (node (ref "C7") (pin "2") (pinfunction "2_2") (pintype "passive"))
      (node (ref "C8") (pin "2") (pinfunction "2_2") (pintype "passive"))
      (node (ref "C9") (pin "2") (pinfunction "2_2") (pintype "passive"))
      (node (ref "Q2") (pin "3") (pinfunction "E_3") (pintype "passive"))
      (node (ref "Q3") (pin "3") (pinfunction "E_3") (pintype "passive"))
      (node (ref "Q4") (pin "3") (pinfunction "E_3") (pintype "passive"))
      (node (ref "Q5") (pin "3") (pinfunction "E_3") (pintype "passive"))
      (node (ref "Q6") (pin "3") (pinfunction "E_3") (pintype "passive"))
      (node (ref "Q7") (pin "3") (pinfunction "E_3") (pintype "passive"))
      (node (ref "R1") (pin "2") (pinfunction "2_2") (pintype "passive"))
      (node (ref "R11") (pin "2") (pinfunction "2_2") (pintype "passive"))
      (node (ref "R2") (pin "2") (pinfunction "2_2") (pintype "passive"))
      (node (ref "R3") (pin "2") (pinfunction "2_2") (pintype "passive"))
      (node (ref "R5") (pin "2") (pinfunction "2_2") (pintype "passive"))
      (node (ref "R8") (pin "2") (pinfunction "2_2") (pintype "passive"))
      (node (ref "SR1") (pin "1") (pinfunction "VIN_1") (pintype "passive"))
      (node (ref "U1") (pin "3") (pinfunction "OUT_3") (pintype "passive"))
      (node (ref "U2") (pin "1") (pinfunction "VIN_1") (pintype "passive"))
      (node (ref "U3") (pin "1") (pinfunction "VCC2_1") (pintype "passive"))
      (node (ref "U4") (pin "28") (pinfunction "VDD_28") (pintype "passive"))
      (node (ref "U4") (pin "7") (pinfunction "VDD_7") (pintype "passive"))
    )
    (net (code "39") (name "GND") (class "Default")
      (node (ref "BT1") (pin "2") (pinfunction "-_2") (pintype "passive"))
      (node (ref "C1") (pin "1") (pinfunction "1_1") (pintype "passive"))
      (node (ref "C10") (pin "1") (pintype "passive"))
      (node (ref "C11") (pin "1") (pinfunction "1_1") (pintype "passive"))
      (node (ref "C12") (pin "1") (pinfunction "1_1") (pintype "passive"))
      (node (ref "C2") (pin "1") (pinfunction "1_1") (pintype "passive"))
      (node (ref "C3") (pin "1") (pintype "passive"))
      (node (ref "C4") (pin "1") (pintype "passive"))
      (node (ref "C5") (pin "1") (pinfunction "1_1") (pintype "passive"))
      (node (ref "C6") (pin "1") (pinfunction "1_1") (pintype "passive"))
      (node (ref "C7") (pin "1") (pintype "passive"))
      (node (ref "C8") (pin "1") (pintype "passive"))
      (node (ref "C9") (pin "1") (pintype "passive"))
      (node (ref "D1") (pin "2") (pinfunction "2_2") (pintype "passive"))
      (node (ref "D2") (pin "2") (pinfunction "2_2") (pintype "passive"))
      (node (ref "D3") (pin "2") (pinfunction "2_2") (pintype "passive"))
      (node (ref "D4") (pin "2") (pinfunction "2_2") (pintype "passive"))
      (node (ref "D5") (pin "2") (pinfunction "2_2") (pintype "passive"))
      (node (ref "D6") (pin "2") (pinfunction "2_2") (pintype "passive"))
      (node (ref "D7") (pin "2") (pinfunction "2_2") (pintype "passive"))
      (node (ref "D8") (pin "2") (pinfunction "2_2") (pintype "passive"))
      (node (ref "LS1") (pin "1") (pinfunction "+_1") (pintype "passive"))
      (node (ref "R10") (pin "2") (pinfunction "2_2") (pintype "passive"))
      (node (ref "R14") (pin "2") (pinfunction "2_2") (pintype "passive"))
      (node (ref "R4") (pin "2") (pinfunction "2_2") (pintype "passive"))
      (node (ref "R6") (pin "2") (pinfunction "2_2") (pintype "passive"))
      (node (ref "R7") (pin "1") (pinfunction "1_1") (pintype "passive"))
      (node (ref "SR1") (pin "3") (pinfunction "GND_3") (pintype "passive"))
      (node (ref "SW3") (pin "1") (pinfunction "1_1") (pintype "passive"))
      (node (ref "U1") (pin "2") (pinfunction "GND_2") (pintype "passive"))
      (node (ref "U2") (pin "2") (pinfunction "GND_2") (pintype "passive"))
      (node (ref "U3") (pin "4") (pinfunction "GND_4") (pintype "passive"))
      (node (ref "U4") (pin "29") (pinfunction "VSS_29") (pintype "passive"))
      (node (ref "U4") (pin "6") (pinfunction "VSS_6") (pintype "passive"))
    )
    (net (code "40") (name "Net-(BT1-+)") (class "Default")
      (node (ref "BT1") (pin "1") (pinfunction "+_1") (pintype "passive"))
      (node (ref "C1") (pin "2") (pinfunction "2_2") (pintype "passive"))
      (node (ref "U1") (pin "1") (pinfunction "IN_1") (pintype "passive"))
    )
    (net (code "41") (name "Net-(D1-Pad1)") (class "Default")
      (node (ref "D1") (pin "1") (pinfunction "1_1") (pintype "passive"))
      (node (ref "R12") (pin "2") (pinfunction "2_2") (pintype "passive"))
    )
    (net (code "42") (name "Net-(D2-Pad1)") (class "Default")
      (node (ref "D2") (pin "1") (pinfunction "1_1") (pintype "passive"))
      (node (ref "R13") (pin "2") (pinfunction "2_2") (pintype "passive"))
    )
    (net (code "43") (name "Net-(LS1--)") (class "Default")
      (node (ref "LS1") (pin "2") (pinfunction "-_2") (pintype "passive"))
      (node (ref "Q1") (pin "3") (pinfunction "E_3") (pintype "passive"))
      (node (ref "R7") (pin "2") (pinfunction "2_2") (pintype "passive"))
    )
    (net (code "44") (name "Net-(Q1-C)") (class "Default")
      (node (ref "Q1") (pin "1") (pinfunction "C_1") (pintype "passive"))
      (node (ref "R1") (pin "1") (pinfunction "1_1") (pintype "passive"))
    )
    (net (code "45") (name "Net-(Q2-B)") (class "Default")
      (node (ref "Q2") (pin "2") (pinfunction "B_2") (pintype "passive"))
      (node (ref "R15") (pin "2") (pinfunction "2_2") (pintype "passive"))
    )
    (net (code "46") (name "Net-(Q3-B)") (class "Default")
      (node (ref "Q3") (pin "2") (pinfunction "B_2") (pintype "passive"))
      (node (ref "R16") (pin "2") (pinfunction "2_2") (pintype "passive"))
    )
    (net (code "47") (name "Net-(Q4-B)") (class "Default")
      (node (ref "Q4") (pin "2") (pinfunction "B_2") (pintype "passive"))
      (node (ref "R17") (pin "2") (pinfunction "2_2") (pintype "passive"))
    )
    (net (code "48") (name "Net-(Q5-B)") (class "Default")
      (node (ref "Q5") (pin "2") (pinfunction "B_2") (pintype "passive"))
      (node (ref "R25") (pin "2") (pinfunction "2_2") (pintype "passive"))
    )
    (net (code "49") (name "Net-(Q6-B)") (class "Default")
      (node (ref "Q6") (pin "2") (pinfunction "B_2") (pintype "passive"))
      (node (ref "R26") (pin "2") (pinfunction "2_2") (pintype "passive"))
    )
    (net (code "50") (name "Net-(Q7-B)") (class "Default")
      (node (ref "Q7") (pin "2") (pinfunction "B_2") (pintype "passive"))
      (node (ref "R27") (pin "2") (pinfunction "2_2") (pintype "passive"))
    )
    (net (code "51") (name "Net-(R2-Pad1)") (class "Default")
      (node (ref "R2") (pin "1") (pinfunction "1_1") (pintype "passive"))
      (node (ref "SW1") (pin "2") (pinfunction "2_2") (pintype "passive"))
    )
    (net (code "52") (name "Net-(R5-Pad1)") (class "Default")
      (node (ref "R5") (pin "1") (pinfunction "1_1") (pintype "passive"))
      (node (ref "SW2") (pin "2") (pinfunction "2_2") (pintype "passive"))
    )
    (net (code "53") (name "Net-(R8-Pad1)") (class "Default")
      (node (ref "R8") (pin "1") (pinfunction "1_1") (pintype "passive"))
      (node (ref "SW4") (pin "2") (pinfunction "2_2") (pintype "passive"))
    )
    (net (code "54") (name "Net-(R11-Pad1)") (class "Default")
      (node (ref "R11") (pin "1") (pinfunction "1_1") (pintype "passive"))
      (node (ref "SW5") (pin "2") (pinfunction "2_2") (pintype "passive"))
    )
    (net (code "55") (name "Net-(SR1-VOUT)") (class "Default")
      (node (ref "SR1") (pin "2") (pinfunction "VOUT_2") (pintype "passive"))
      (node (ref "U4") (pin "19") (pinfunction "RA0/AN0_19") (pintype "passive"))
    )
    (net (code "56") (name "Net-(U3-X1)") (class "Default")
      (node (ref "U3") (pin "2") (pinfunction "X1_2") (pintype "passive"))
      (node (ref "XTAL1") (pin "1") (pinfunction "1_1") (pintype "passive"))
    )
    (net (code "57") (name "Net-(U3-X2)") (class "Default")
      (node (ref "U3") (pin "3") (pinfunction "X2_3") (pintype "passive"))
      (node (ref "XTAL1") (pin "2") (pinfunction "2_2") (pintype "passive"))
    )
    (net (code "58") (name "Net-(U4-OSC1{slash}CLKI)") (class "Default")
      (node (ref "C11") (pin "2") (pinfunction "2_2") (pintype "passive"))
      (node (ref "U4") (pin "30") (pinfunction "OSC1/CLKI_30") (pintype "passive"))
      (node (ref "XTAL2") (pin "2") (pinfunction "2_2") (pintype "passive"))
    )
    (net (code "59") (name "Net-(U4-OSC2{slash}CLKO)") (class "Default")
      (node (ref "C12") (pin "2") (pinfunction "2_2") (pintype "passive"))
      (node (ref "U4") (pin "31") (pinfunction "OSC2/CLKO_31") (pintype "passive"))
      (node (ref "XTAL2") (pin "1") (pinfunction "1_1") (pintype "passive"))
    )
    (net (code "60") (name "Net-(U4-RA2{slash}AN2{slash}VREF-)") (class "Default")
      (node (ref "R9") (pin "1") (pinfunction "1_1") (pintype "passive"))
      (node (ref "U4") (pin "21") (pinfunction "RA2/AN2/VREF-_21") (pintype "passive"))
    )
    (net (code "61") (name "Net-(U4-RE0{slash}AN5{slash}~{RD})") (class "Default")
      (node (ref "R12") (pin "1") (pinfunction "1_1") (pintype "passive"))
      (node (ref "U4") (pin "25") (pinfunction "RE0/AN5/~{RD}_25") (pintype "passive"))
    )
    (net (code "62") (name "Net-(U4-RE1{slash}AN6{slash}~{WR})") (class "Default")
      (node (ref "R13") (pin "1") (pinfunction "1_1") (pintype "passive"))
      (node (ref "U4") (pin "26") (pinfunction "RE1/AN6/~{WR}_26") (pintype "passive"))
    )
    (net (code "63") (name "Net-(U4-~{MCLR}{slash}VPP)") (class "Default")
      (node (ref "R3") (pin "1") (pinfunction "1_1") (pintype "passive"))
      (node (ref "SW3") (pin "2") (pinfunction "2_2") (pintype "passive"))
      (node (ref "U4") (pin "18") (pinfunction "~{MCLR}/VPP_18") (pintype "passive"))
    )
    (net (code "64") (name "unconnected-(DS1-PadDP)") (class "Default")
      (node (ref "DS1") (pin "DP") (pinfunction "DP_DP") (pintype "passive"))
    )
    (net (code "65") (name "unconnected-(DS2-PadDP)") (class "Default")
      (node (ref "DS2") (pin "DP") (pinfunction "DP_DP") (pintype "passive"))
    )
    (net (code "66") (name "unconnected-(DS3-PadDP)") (class "Default")
      (node (ref "DS3") (pin "DP") (pinfunction "DP_DP") (pintype "passive"))
    )
    (net (code "67") (name "unconnected-(DS4-PadDP)") (class "Default")
      (node (ref "DS4") (pin "DP") (pinfunction "DP_DP") (pintype "passive"))
    )
    (net (code "68") (name "unconnected-(DS5-PadDP)") (class "Default")
      (node (ref "DS5") (pin "DP") (pinfunction "DP_DP") (pintype "passive"))
    )
    (net (code "69") (name "unconnected-(DS6-PadDP)") (class "Default")
      (node (ref "DS6") (pin "DP") (pinfunction "DP_DP") (pintype "passive"))
    )
    (net (code "70") (name "unconnected-(U4-NC-Pad12)") (class "Default")
      (node (ref "U4") (pin "12") (pinfunction "NC_12") (pintype "passive"))
    )
    (net (code "71") (name "unconnected-(U4-NC-Pad13)") (class "Default")
      (node (ref "U4") (pin "13") (pinfunction "NC_13") (pintype "passive"))
    )
    (net (code "72") (name "unconnected-(U4-NC-Pad33)") (class "Default")
      (node (ref "U4") (pin "33") (pinfunction "NC_33") (pintype "passive"))
    )
    (net (code "73") (name "unconnected-(U4-NC-Pad34)") (class "Default")
      (node (ref "U4") (pin "34") (pinfunction "NC_34") (pintype "passive"))
    )
    (net (code "74") (name "unconnected-(U4-RA3{slash}AN3{slash}VREF+-Pad22)") (class "Default")
      (node (ref "U4") (pin "22") (pinfunction "RA3/AN3/VREF+_22") (pintype "passive"))
    )
    (net (code "75") (name "unconnected-(U4-RA4{slash}T0CKI{slash}C1OUT-Pad23)") (class "Default")
      (node (ref "U4") (pin "23") (pinfunction "RA4/T0CKI/C1OUT_23") (pintype "passive"))
    )
    (net (code "76") (name "unconnected-(U4-RA5{slash}AN4{slash}C2OUT{slash}~{SS}-Pad24)") (class "Default")
      (node (ref "U4") (pin "24") (pinfunction "RA5/AN4/C2OUT/~{SS}_24") (pintype "passive"))
    )
    (net (code "77") (name "unconnected-(U4-RB7{slash}PGD-Pad17)") (class "Default")
      (node (ref "U4") (pin "17") (pinfunction "RB7/PGD_17") (pintype "passive"))
    )
    (net (code "78") (name "unconnected-(U4-RD6{slash}PDP6-Pad4)") (class "Default")
      (node (ref "U4") (pin "4") (pinfunction "RD6/PDP6_4") (pintype "passive"))
    )
    (net (code "79") (name "unconnected-(U4-RD7{slash}PSP7-Pad5)") (class "Default")
      (node (ref "U4") (pin "5") (pinfunction "RD7/PSP7_5") (pintype "passive"))
    )
    (net (code "80") (name "unconnected-(U4-RE2{slash}AN7{slash}~{CS}-Pad27)") (class "Default")
      (node (ref "U4") (pin "27") (pinfunction "RE2/AN7/~{CS}_27") (pintype "passive"))
    )
  )
)
